# SNES_TST_Sheet1.net
KiCad netlist of a schematic drawn in Altium Designer
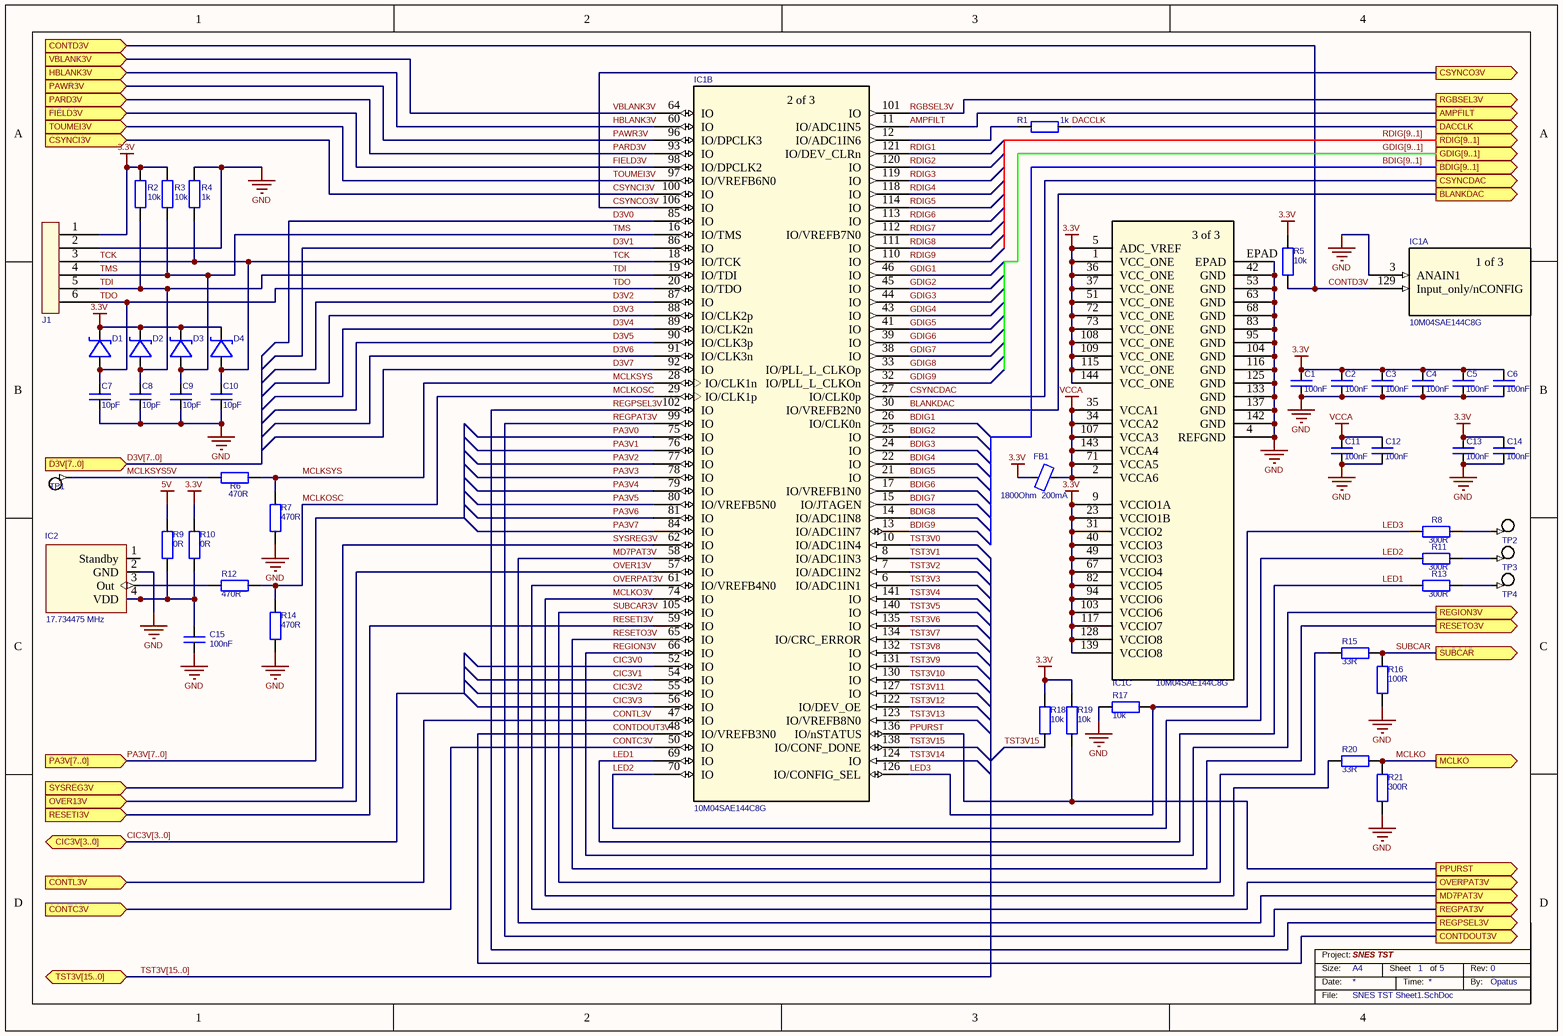
[diagram p0: SNES TST Sheet1.SchDoc]

(export (version "E")
  (design (tool "Eeschema 10.0.6"))
  (components
    (comp (ref "C1")
      (value "100nF")
      (footprint "Cap_0402_Chip")
      (fields (field (name "TOLERANCE") "+-20%"))
      (libsource (lib "PCB") (part "Capacitor"))
    )
    (comp (ref "C2")
      (value "100nF")
      (footprint "Cap_0402_Chip")
      (fields (field (name "TOLERANCE") "+-20%"))
      (libsource (lib "PCB") (part "Capacitor"))
    )
    (comp (ref "C3")
      (value "100nF")
      (footprint "Cap_0402_Chip")
      (fields (field (name "TOLERANCE") "+-20%"))
      (libsource (lib "PCB") (part "Capacitor"))
    )
    (comp (ref "C4")
      (value "100nF")
      (footprint "Cap_0402_Chip")
      (fields (field (name "TOLERANCE") "+-20%"))
      (libsource (lib "PCB") (part "Capacitor"))
    )
    (comp (ref "C5")
      (value "100nF")
      (footprint "Cap_0402_Chip")
      (fields (field (name "TOLERANCE") "+-20%"))
      (libsource (lib "PCB") (part "Capacitor"))
    )
    (comp (ref "C6")
      (value "100nF")
      (footprint "Cap_0402_Chip")
      (fields (field (name "TOLERANCE") "+-20%"))
      (libsource (lib "PCB") (part "Capacitor"))
    )
    (comp (ref "C7")
      (value "10pF")
      (footprint "Cap_0402_Chip")
      (fields (field (name "TOLERANCE") "+-20%"))
      (libsource (lib "PCB") (part "Capacitor"))
    )
    (comp (ref "C8")
      (value "10pF")
      (footprint "Cap_0402_Chip")
      (fields (field (name "TOLERANCE") "+-20%"))
      (libsource (lib "PCB") (part "Capacitor"))
    )
    (comp (ref "C9")
      (value "10pF")
      (footprint "Cap_0402_Chip")
      (fields (field (name "TOLERANCE") "+-20%"))
      (libsource (lib "PCB") (part "Capacitor"))
    )
    (comp (ref "C10")
      (value "10pF")
      (footprint "Cap_0402_Chip")
      (fields (field (name "TOLERANCE") "+-20%"))
      (libsource (lib "PCB") (part "Capacitor"))
    )
    (comp (ref "C11")
      (value "100nF")
      (footprint "Cap_0402_Chip")
      (fields (field (name "TOLERANCE") "+-20%"))
      (libsource (lib "PCB") (part "Capacitor"))
    )
    (comp (ref "C12")
      (value "100nF")
      (footprint "Cap_0402_Chip")
      (fields (field (name "TOLERANCE") "+-20%"))
      (libsource (lib "PCB") (part "Capacitor"))
    )
    (comp (ref "C13")
      (value "100nF")
      (footprint "Cap_0402_Chip")
      (fields (field (name "TOLERANCE") "+-20%"))
      (libsource (lib "PCB") (part "Capacitor"))
    )
    (comp (ref "C14")
      (value "100nF")
      (footprint "Cap_0402_Chip")
      (fields (field (name "TOLERANCE") "+-20%"))
      (libsource (lib "PCB") (part "Capacitor"))
    )
    (comp (ref "C15")
      (value "100nF")
      (footprint "Cap_0402_Chip")
      (fields (field (name "TOLERANCE") "+-20%"))
      (libsource (lib "PCB") (part "Capacitor"))
    )
    (comp (ref "D1")
      (value "Schottky Diode")
      (footprint "SOD323")
      (fields (field (name "MANUFACTURER_PART_NUMBER") "BAT54WS-7-F"))
      (libsource (lib "PCB") (part "Schottky Diode"))
    )
    (comp (ref "D2")
      (value "Schottky Diode")
      (footprint "SOD323")
      (fields (field (name "MANUFACTURER_PART_NUMBER") "BAT54WS-7-F"))
      (libsource (lib "PCB") (part "Schottky Diode"))
    )
    (comp (ref "D3")
      (value "Schottky Diode")
      (footprint "SOD323")
      (fields (field (name "MANUFACTURER_PART_NUMBER") "BAT54WS-7-F"))
      (libsource (lib "PCB") (part "Schottky Diode"))
    )
    (comp (ref "D4")
      (value "Schottky Diode")
      (footprint "SOD323")
      (fields (field (name "MANUFACTURER_PART_NUMBER") "BAT54WS-7-F"))
      (libsource (lib "PCB") (part "Schottky Diode"))
    )
    (comp (ref "FB1")
      (value "1800Ohm  200mA")
      (footprint "Ind_0402_Chip")
      (fields (field (name "MANUFACTURER_PART_NUMBER") "MMZ1005S182ET000"))
      (libsource (lib "PCB") (part "Ferrite Bead"))
    )
    (comp (ref "IC1")
      (value "10M04SAE144C8G")
      (footprint "EQFP-144_A:1P65_")
      (description "No Description Available")
      (fields
        (field (name "MANUFACTURER_PART_NUMBER") "10M08SAE144C8G")
        (field (name "COPYRIGHT") "Copyright (C) 2018 Accelerated Designs. All rights reserved")
      )
      (libsource (lib "") (part "10M08SAE144C8G_1"))
    )
    (comp (ref "IC2")
      (value "17.734475 MHz")
      (footprint "Quarz 7.5mm")
      (description "Oscillator")
      (fields
        (field (name "FREQUENCY") "17.734475 MHz")
        (field (name "MANUFACTURER_PART_NUMBER") "LFSPXO020648Bulk")
      )
      (libsource (lib "PCB") (part "Oscillator"))
    )
    (comp (ref "J1")
      (value "Conn 6P")
      (footprint "Con6P")
      (description "6 Pole Connector")
      (libsource (lib "PCB") (part "Conn 6P"))
    )
    (comp (ref "R1")
      (value "1k")
      (footprint "Res_0402_Chip")
      (fields (field (name "TOLERANCE") "+-1%"))
      (libsource (lib "") (part "R_1"))
    )
    (comp (ref "R2")
      (value "10k")
      (footprint "Res_0402_Chip")
      (fields (field (name "TOLERANCE") "+-1%"))
      (libsource (lib "") (part "R_2"))
    )
    (comp (ref "R3")
      (value "10k")
      (footprint "Res_0402_Chip")
      (fields (field (name "TOLERANCE") "+-1%"))
      (libsource (lib "") (part "R_2"))
    )
    (comp (ref "R4")
      (value "1k")
      (footprint "Res_0402_Chip")
      (fields (field (name "TOLERANCE") "+-1%"))
      (libsource (lib "") (part "R_3"))
    )
    (comp (ref "R5")
      (value "10k")
      (footprint "Res_0402_Chip")
      (fields (field (name "TOLERANCE") "+-1%"))
      (libsource (lib "") (part "R_2"))
    )
    (comp (ref "R6")
      (value "470R")
      (footprint "Res_0603_Chip")
      (fields (field (name "TOLERANCE") "+-1%"))
      (libsource (lib "PCB") (part "R"))
    )
    (comp (ref "R7")
      (value "470R")
      (footprint "Res_0603_Chip")
      (fields (field (name "TOLERANCE") "+-1%"))
      (libsource (lib "") (part "R_2"))
    )
    (comp (ref "R8")
      (value "300R")
      (footprint "Res_0603_Chip")
      (fields (field (name "TOLERANCE") "+-1%"))
      (libsource (lib "PCB") (part "R"))
    )
    (comp (ref "R9") (value "0R") (footprint "Res_0402_Chip") (libsource (lib "") (part "R_2")))
    (comp (ref "R10") (value "0R") (footprint "Res_0402_Chip") (libsource (lib "") (part "R_2")))
    (comp (ref "R11")
      (value "300R")
      (footprint "Res_0603_Chip")
      (fields (field (name "TOLERANCE") "+-1%"))
      (libsource (lib "PCB") (part "R"))
    )
    (comp (ref "R12")
      (value "470R")
      (footprint "Res_0603_Chip")
      (fields (field (name "TOLERANCE") "+-1%"))
      (libsource (lib "PCB") (part "R"))
    )
    (comp (ref "R13")
      (value "300R")
      (footprint "Res_0603_Chip")
      (fields (field (name "TOLERANCE") "+-1%"))
      (libsource (lib "PCB") (part "R"))
    )
    (comp (ref "R14")
      (value "470R")
      (footprint "Res_0603_Chip")
      (fields (field (name "TOLERANCE") "+-1%"))
      (libsource (lib "") (part "R_2"))
    )
    (comp (ref "R15")
      (value "33R")
      (footprint "Res_0603_Chip")
      (fields (field (name "TOLERANCE") "+-1%"))
      (libsource (lib "PCB") (part "R"))
    )
    (comp (ref "R16")
      (value "100R")
      (footprint "Res_0603_Chip")
      (fields (field (name "TOLERANCE") "+-1%"))
      (libsource (lib "") (part "R_2"))
    )
    (comp (ref "R17")
      (value "10k")
      (footprint "Res_0402_Chip")
      (fields (field (name "TOLERANCE") "+-1%"))
      (libsource (lib "") (part "R_1"))
    )
    (comp (ref "R18")
      (value "10k")
      (footprint "Res_0402_Chip")
      (fields (field (name "TOLERANCE") "+-1%"))
      (libsource (lib "") (part "R_2"))
    )
    (comp (ref "R19")
      (value "10k")
      (footprint "Res_0402_Chip")
      (fields (field (name "TOLERANCE") "+-1%"))
      (libsource (lib "") (part "R_2"))
    )
    (comp (ref "R20")
      (value "33R")
      (footprint "Res_0603_Chip")
      (fields (field (name "TOLERANCE") "+-1%"))
      (libsource (lib "PCB") (part "R"))
    )
    (comp (ref "R21")
      (value "300R")
      (footprint "Res_0603_Chip")
      (fields (field (name "TOLERANCE") "+-1%"))
      (libsource (lib "") (part "R_2"))
    )
    (comp (ref "TP1")
      (value "Pin Connector")
      (footprint "Pin Connector Small")
      (libsource (lib "PCB") (part "Pin Connector"))
    )
    (comp (ref "TP2")
      (value "Pin Connector")
      (footprint "Pin Connector Small")
      (libsource (lib "PCB") (part "Pin Connector"))
    )
    (comp (ref "TP3")
      (value "Pin Connector")
      (footprint "Pin Connector Small")
      (libsource (lib "PCB") (part "Pin Connector"))
    )
    (comp (ref "TP4")
      (value "Pin Connector")
      (footprint "Pin Connector Small")
      (libsource (lib "PCB") (part "Pin Connector"))
    )
  )
  (nets
    (net (code "1") (name "/AMPFILT") (class "Default")
      (node (ref "IC1") (pin "11") (pinfunction "IO/ADC1IN5_11") (pintype "output"))
    )
    (net (code "2") (name "/BDIG1") (class "Default")
      (node (ref "IC1") (pin "26") (pinfunction "IO/CLK0n_26") (pintype "output"))
    )
    (net (code "3") (name "/BDIG2") (class "Default")
      (node (ref "IC1") (pin "25") (pinfunction "IO_25") (pintype "output"))
    )
    (net (code "4") (name "/BDIG3") (class "Default")
      (node (ref "IC1") (pin "24") (pinfunction "IO_24") (pintype "output"))
    )
    (net (code "5") (name "/BDIG4") (class "Default")
      (node (ref "IC1") (pin "22") (pinfunction "IO_22") (pintype "output"))
    )
    (net (code "6") (name "/BDIG5") (class "Default")
      (node (ref "IC1") (pin "21") (pinfunction "IO_21") (pintype "output"))
    )
    (net (code "7") (name "/BDIG6") (class "Default")
      (node (ref "IC1") (pin "17") (pinfunction "IO/VREFB1N0_17") (pintype "output"))
    )
    (net (code "8") (name "/BDIG7") (class "Default")
      (node (ref "IC1") (pin "15") (pinfunction "IO/JTAGEN_15") (pintype "output"))
    )
    (net (code "9") (name "/BDIG8") (class "Default")
      (node (ref "IC1") (pin "14") (pinfunction "IO/ADC1IN8_14") (pintype "output"))
    )
    (net (code "10") (name "/BDIG9") (class "Default")
      (node (ref "IC1") (pin "13") (pinfunction "IO/ADC1IN7_13") (pintype "bidirectional"))
    )
    (net (code "12") (name "/BLANKDAC") (class "Default")
      (node (ref "IC1") (pin "30") (pinfunction "IO/VREFB2N0_30") (pintype "output"))
    )
    (net (code "13") (name "/CIC3V0") (class "Default")
      (node (ref "IC1") (pin "52") (pinfunction "IO_52") (pintype "bidirectional"))
    )
    (net (code "14") (name "/CIC3V1") (class "Default")
      (node (ref "IC1") (pin "54") (pinfunction "IO_54") (pintype "bidirectional"))
    )
    (net (code "15") (name "/CIC3V2") (class "Default")
      (node (ref "IC1") (pin "55") (pinfunction "IO_55") (pintype "bidirectional"))
    )
    (net (code "16") (name "/CIC3V3") (class "Default")
      (node (ref "IC1") (pin "56") (pinfunction "IO_56") (pintype "bidirectional"))
    )
    (net (code "18") (name "/CONTC3V") (class "Default")
      (node (ref "IC1") (pin "50") (pinfunction "IO_50") (pintype "bidirectional"))
    )
    (net (code "19") (name "/CONTD3V") (class "Default")
      (node (ref "IC1") (pin "129") (pinfunction "Input_only/nCONFIG_129") (pintype "input"))
      (node (ref "R5") (pin "2") (pintype "passive"))
    )
    (net (code "20") (name "/CONTDOUT3V") (class "Default")
      (node (ref "IC1") (pin "48") (pinfunction "IO/VREFB3N0_48") (pintype "bidirectional"))
    )
    (net (code "21") (name "/CONTL3V") (class "Default")
      (node (ref "IC1") (pin "47") (pinfunction "IO_47") (pintype "bidirectional"))
    )
    (net (code "22") (name "/CSYNCDAC") (class "Default")
      (node (ref "IC1") (pin "27") (pinfunction "IO/CLK0p_27") (pintype "output"))
    )
    (net (code "23") (name "/CSYNCI3V") (class "Default")
      (node (ref "IC1") (pin "100") (pinfunction "IO_100") (pintype "bidirectional"))
    )
    (net (code "24") (name "/CSYNCO3V") (class "Default")
      (node (ref "IC1") (pin "106") (pinfunction "IO_106") (pintype "bidirectional"))
    )
    (net (code "25") (name "/D3V0") (class "Default")
      (node (ref "IC1") (pin "85") (pinfunction "IO_85") (pintype "bidirectional"))
    )
    (net (code "26") (name "/D3V1") (class "Default")
      (node (ref "IC1") (pin "86") (pinfunction "IO_86") (pintype "bidirectional"))
    )
    (net (code "27") (name "/D3V2") (class "Default")
      (node (ref "IC1") (pin "87") (pinfunction "IO_87") (pintype "bidirectional"))
    )
    (net (code "28") (name "/D3V3") (class "Default")
      (node (ref "IC1") (pin "88") (pinfunction "IO/CLK2p_88") (pintype "bidirectional"))
    )
    (net (code "29") (name "/D3V4") (class "Default")
      (node (ref "IC1") (pin "89") (pinfunction "IO/CLK2n_89") (pintype "bidirectional"))
    )
    (net (code "30") (name "/D3V5") (class "Default")
      (node (ref "IC1") (pin "90") (pinfunction "IO/CLK3p_90") (pintype "bidirectional"))
    )
    (net (code "31") (name "/D3V6") (class "Default")
      (node (ref "IC1") (pin "91") (pinfunction "IO/CLK3n_91") (pintype "bidirectional"))
    )
    (net (code "32") (name "/D3V7") (class "Default")
      (node (ref "IC1") (pin "92") (pinfunction "IO_92") (pintype "bidirectional"))
    )
    (net (code "34") (name "/DACCLK") (class "Default") (node (ref "R1") (pin "2") (pintype "passive")))
    (net (code "35") (name "/FIELD3V") (class "Default")
      (node (ref "IC1") (pin "98") (pinfunction "IO/DPCLK2_98") (pintype "bidirectional"))
    )
    (net (code "36") (name "/GDIG1") (class "Default")
      (node (ref "IC1") (pin "46") (pinfunction "IO_46") (pintype "output"))
    )
    (net (code "37") (name "/GDIG2") (class "Default")
      (node (ref "IC1") (pin "45") (pinfunction "IO_45") (pintype "output"))
    )
    (net (code "38") (name "/GDIG3") (class "Default")
      (node (ref "IC1") (pin "44") (pinfunction "IO_44") (pintype "output"))
    )
    (net (code "39") (name "/GDIG4") (class "Default")
      (node (ref "IC1") (pin "43") (pinfunction "IO_43") (pintype "output"))
    )
    (net (code "40") (name "/GDIG5") (class "Default")
      (node (ref "IC1") (pin "41") (pinfunction "IO_41") (pintype "output"))
    )
    (net (code "41") (name "/GDIG6") (class "Default")
      (node (ref "IC1") (pin "39") (pinfunction "IO_39") (pintype "output"))
    )
    (net (code "42") (name "/GDIG7") (class "Default")
      (node (ref "IC1") (pin "38") (pinfunction "IO_38") (pintype "output"))
    )
    (net (code "43") (name "/GDIG8") (class "Default")
      (node (ref "IC1") (pin "33") (pinfunction "IO/PLL_L_CLKOp_33") (pintype "output"))
    )
    (net (code "44") (name "/GDIG9") (class "Default")
      (node (ref "IC1") (pin "32") (pinfunction "IO/PLL_L_CLKOn_32") (pintype "output"))
    )
    (net (code "46") (name "/HBLANK3V") (class "Default")
      (node (ref "IC1") (pin "60") (pinfunction "IO_60") (pintype "bidirectional"))
    )
    (net (code "47") (name "/LED1") (class "Default")
      (node (ref "IC1") (pin "69") (pinfunction "IO_69") (pintype "bidirectional"))
      (node (ref "R13") (pin "2") (pintype "passive"))
    )
    (net (code "48") (name "/LED2") (class "Default")
      (node (ref "IC1") (pin "70") (pinfunction "IO_70") (pintype "bidirectional"))
      (node (ref "R11") (pin "2") (pintype "passive"))
    )
    (net (code "49") (name "/LED3") (class "Default")
      (node (ref "IC1") (pin "126") (pinfunction "IO/CONFIG_SEL_126") (pintype "bidirectional"))
      (node (ref "R17") (pin "2") (pintype "passive"))
      (node (ref "R8") (pin "2") (pintype "passive"))
    )
    (net (code "50") (name "/MCLKO") (class "Default")
      (node (ref "R20") (pin "1") (pintype "passive"))
      (node (ref "R21") (pin "1") (pintype "passive"))
    )
    (net (code "51") (name "/MCLKO3V") (class "Default")
      (node (ref "IC1") (pin "74") (pinfunction "IO_74") (pintype "bidirectional"))
      (node (ref "R20") (pin "2") (pintype "passive"))
    )
    (net (code "52") (name "/MCLKOSC") (class "Default")
      (node (ref "IC1") (pin "29") (pinfunction "IO/CLK1p_29") (pintype "bidirectional"))
      (node (ref "R12") (pin "1") (pintype "passive"))
      (node (ref "R14") (pin "1") (pintype "passive"))
    )
    (net (code "53") (name "/MCLKSYS") (class "Default")
      (node (ref "IC1") (pin "28") (pinfunction "IO/CLK1n_28") (pintype "bidirectional"))
      (node (ref "R6") (pin "1") (pintype "passive"))
      (node (ref "R7") (pin "1") (pintype "passive"))
    )
    (net (code "54") (name "/MCLKSYS5V") (class "Default")
      (node (ref "R6") (pin "2") (pintype "passive"))
      (node (ref "TP1") (pin "1") (pinfunction "0_1") (pintype "output"))
    )
    (net (code "55") (name "/MD7PAT3V") (class "Default")
      (node (ref "IC1") (pin "58") (pinfunction "IO_58") (pintype "bidirectional"))
    )
    (net (code "56") (name "/OVER13V") (class "Default")
      (node (ref "IC1") (pin "57") (pinfunction "IO_57") (pintype "bidirectional"))
    )
    (net (code "57") (name "/OVERPAT3V") (class "Default")
      (node (ref "IC1") (pin "61") (pinfunction "IO/VREFB4N0_61") (pintype "bidirectional"))
    )
    (net (code "58") (name "/PA3V0") (class "Default")
      (node (ref "IC1") (pin "75") (pinfunction "IO_75") (pintype "bidirectional"))
    )
    (net (code "59") (name "/PA3V1") (class "Default")
      (node (ref "IC1") (pin "76") (pinfunction "IO_76") (pintype "bidirectional"))
    )
    (net (code "60") (name "/PA3V2") (class "Default")
      (node (ref "IC1") (pin "77") (pinfunction "IO_77") (pintype "bidirectional"))
    )
    (net (code "61") (name "/PA3V3") (class "Default")
      (node (ref "IC1") (pin "78") (pinfunction "IO_78") (pintype "bidirectional"))
    )
    (net (code "62") (name "/PA3V4") (class "Default")
      (node (ref "IC1") (pin "79") (pinfunction "IO_79") (pintype "bidirectional"))
    )
    (net (code "63") (name "/PA3V5") (class "Default")
      (node (ref "IC1") (pin "80") (pinfunction "IO/VREFB5N0_80") (pintype "bidirectional"))
    )
    (net (code "64") (name "/PA3V6") (class "Default")
      (node (ref "IC1") (pin "81") (pinfunction "IO_81") (pintype "bidirectional"))
    )
    (net (code "65") (name "/PA3V7") (class "Default")
      (node (ref "IC1") (pin "84") (pinfunction "IO_84") (pintype "bidirectional"))
    )
    (net (code "67") (name "/PARD3V") (class "Default")
      (node (ref "IC1") (pin "93") (pinfunction "IO_93") (pintype "bidirectional"))
    )
    (net (code "68") (name "/PAWR3V") (class "Default")
      (node (ref "IC1") (pin "96") (pinfunction "IO/DPCLK3_96") (pintype "bidirectional"))
    )
    (net (code "69") (name "/PPURST") (class "Default")
      (node (ref "IC1") (pin "136") (pinfunction "IO/nSTATUS_136") (pintype "bidirectional"))
      (node (ref "R19") (pin "2") (pintype "passive"))
    )
    (net (code "70") (name "/RDIG1") (class "Default")
      (node (ref "IC1") (pin "121") (pinfunction "IO/DEV_CLRn_121") (pintype "output"))
    )
    (net (code "71") (name "/RDIG2") (class "Default")
      (node (ref "IC1") (pin "120") (pinfunction "IO_120") (pintype "output"))
    )
    (net (code "72") (name "/RDIG3") (class "Default")
      (node (ref "IC1") (pin "119") (pinfunction "IO_119") (pintype "output"))
    )
    (net (code "73") (name "/RDIG4") (class "Default")
      (node (ref "IC1") (pin "118") (pinfunction "IO_118") (pintype "output"))
    )
    (net (code "74") (name "/RDIG5") (class "Default")
      (node (ref "IC1") (pin "114") (pinfunction "IO_114") (pintype "output"))
    )
    (net (code "75") (name "/RDIG6") (class "Default")
      (node (ref "IC1") (pin "113") (pinfunction "IO_113") (pintype "output"))
    )
    (net (code "76") (name "/RDIG7") (class "Default")
      (node (ref "IC1") (pin "112") (pinfunction "IO/VREFB7N0_112") (pintype "output"))
    )
    (net (code "77") (name "/RDIG8") (class "Default")
      (node (ref "IC1") (pin "111") (pinfunction "IO_111") (pintype "output"))
    )
    (net (code "78") (name "/RDIG9") (class "Default")
      (node (ref "IC1") (pin "110") (pinfunction "IO_110") (pintype "output"))
    )
    (net (code "80") (name "/REGION3V") (class "Default")
      (node (ref "IC1") (pin "66") (pinfunction "IO_66") (pintype "bidirectional"))
    )
    (net (code "81") (name "/REGPAT3V") (class "Default")
      (node (ref "IC1") (pin "99") (pinfunction "IO_99") (pintype "bidirectional"))
    )
    (net (code "82") (name "/REGPSEL3V") (class "Default")
      (node (ref "IC1") (pin "102") (pinfunction "IO_102") (pintype "bidirectional"))
    )
    (net (code "83") (name "/RESETI3V") (class "Default")
      (node (ref "IC1") (pin "59") (pinfunction "IO_59") (pintype "bidirectional"))
    )
    (net (code "84") (name "/RESETO3V") (class "Default")
      (node (ref "IC1") (pin "65") (pinfunction "IO_65") (pintype "bidirectional"))
    )
    (net (code "85") (name "/RGBSEL3V") (class "Default")
      (node (ref "IC1") (pin "101") (pinfunction "IO_101") (pintype "output"))
    )
    (net (code "86") (name "/SUBCAR") (class "Default")
      (node (ref "R15") (pin "1") (pintype "passive"))
      (node (ref "R16") (pin "1") (pintype "passive"))
    )
    (net (code "87") (name "/SUBCAR3V") (class "Default")
      (node (ref "IC1") (pin "105") (pinfunction "IO_105") (pintype "bidirectional"))
      (node (ref "R15") (pin "2") (pintype "passive"))
    )
    (net (code "88") (name "/SYSREG3V") (class "Default")
      (node (ref "IC1") (pin "62") (pinfunction "IO_62") (pintype "bidirectional"))
    )
    (net (code "89") (name "/TCK") (class "Default")
      (node (ref "C10") (pin "1") (pintype "passive"))
      (node (ref "D4") (pin "2") (pinfunction "A_2") (pintype "passive"))
      (node (ref "IC1") (pin "18") (pinfunction "IO/TCK_18") (pintype "bidirectional"))
      (node (ref "J1") (pin "3") (pintype "passive"))
      (node (ref "R4") (pin "1") (pintype "passive"))
    )
    (net (code "90") (name "/TDI") (class "Default")
      (node (ref "C8") (pin "1") (pintype "passive"))
      (node (ref "D2") (pin "2") (pinfunction "A_2") (pintype "passive"))
      (node (ref "IC1") (pin "19") (pinfunction "IO/TDI_19") (pintype "bidirectional"))
      (node (ref "J1") (pin "5") (pintype "passive"))
      (node (ref "R2") (pin "2") (pintype "passive"))
    )
    (net (code "91") (name "/TDO") (class "Default")
      (node (ref "C7") (pin "1") (pintype "passive"))
      (node (ref "D1") (pin "2") (pinfunction "A_2") (pintype "passive"))
      (node (ref "IC1") (pin "20") (pinfunction "IO/TDO_20") (pintype "bidirectional"))
      (node (ref "J1") (pin "6") (pintype "passive"))
    )
    (net (code "92") (name "/TMS") (class "Default")
      (node (ref "C9") (pin "1") (pintype "passive"))
      (node (ref "D3") (pin "2") (pinfunction "A_2") (pintype "passive"))
      (node (ref "IC1") (pin "16") (pinfunction "IO/TMS_16") (pintype "bidirectional"))
      (node (ref "J1") (pin "4") (pintype "passive"))
      (node (ref "R3") (pin "2") (pintype "passive"))
    )
    (net (code "93") (name "/TOUMEI3V") (class "Default")
      (node (ref "IC1") (pin "97") (pinfunction "IO/VREFB6N0_97") (pintype "bidirectional"))
    )
    (net (code "94") (name "/TST3V0") (class "Default")
      (node (ref "IC1") (pin "10") (pinfunction "IO/ADC1IN4_10") (pintype "input"))
    )
    (net (code "95") (name "/TST3V1") (class "Default")
      (node (ref "IC1") (pin "8") (pinfunction "IO/ADC1IN3_8") (pintype "input"))
    )
    (net (code "96") (name "/TST3V2") (class "Default")
      (node (ref "IC1") (pin "7") (pinfunction "IO/ADC1IN2_7") (pintype "input"))
    )
    (net (code "97") (name "/TST3V3") (class "Default")
      (node (ref "IC1") (pin "6") (pinfunction "IO/ADC1IN1_6") (pintype "input"))
    )
    (net (code "98") (name "/TST3V4") (class "Default")
      (node (ref "IC1") (pin "141") (pinfunction "IO_141") (pintype "input"))
    )
    (net (code "99") (name "/TST3V5") (class "Default")
      (node (ref "IC1") (pin "140") (pinfunction "IO_140") (pintype "input"))
    )
    (net (code "100") (name "/TST3V6") (class "Default")
      (node (ref "IC1") (pin "135") (pinfunction "IO_135") (pintype "input"))
    )
    (net (code "101") (name "/TST3V7") (class "Default")
      (node (ref "IC1") (pin "134") (pinfunction "IO/CRC_ERROR_134") (pintype "input"))
    )
    (net (code "102") (name "/TST3V8") (class "Default")
      (node (ref "IC1") (pin "132") (pinfunction "IO_132") (pintype "input"))
    )
    (net (code "103") (name "/TST3V9") (class "Default")
      (node (ref "IC1") (pin "131") (pinfunction "IO_131") (pintype "input"))
    )
    (net (code "104") (name "/TST3V10") (class "Default")
      (node (ref "IC1") (pin "130") (pinfunction "IO_130") (pintype "input"))
    )
    (net (code "105") (name "/TST3V11") (class "Default")
      (node (ref "IC1") (pin "127") (pinfunction "IO_127") (pintype "input"))
    )
    (net (code "106") (name "/TST3V12") (class "Default")
      (node (ref "IC1") (pin "122") (pinfunction "IO/DEV_OE_122") (pintype "input"))
    )
    (net (code "107") (name "/TST3V13") (class "Default")
      (node (ref "IC1") (pin "123") (pinfunction "IO/VREFB8N0_123") (pintype "input"))
    )
    (net (code "108") (name "/TST3V14") (class "Default")
      (node (ref "IC1") (pin "124") (pinfunction "IO_124") (pintype "input"))
    )
    (net (code "109") (name "/TST3V15") (class "Default")
      (node (ref "IC1") (pin "138") (pinfunction "IO/CONF_DONE_138") (pintype "bidirectional"))
      (node (ref "R18") (pin "2") (pintype "passive"))
    )
    (net (code "111") (name "/VBLANK3V") (class "Default")
      (node (ref "IC1") (pin "64") (pinfunction "IO_64") (pintype "bidirectional"))
    )
    (net (code "112") (name "3.3V") (class "Default")
      (node (ref "C1") (pin "1") (pintype "passive"))
      (node (ref "C13") (pin "1") (pintype "passive"))
      (node (ref "C14") (pin "1") (pintype "passive"))
      (node (ref "C2") (pin "1") (pintype "passive"))
      (node (ref "C3") (pin "1") (pintype "passive"))
      (node (ref "C4") (pin "1") (pintype "passive"))
      (node (ref "C5") (pin "1") (pintype "passive"))
      (node (ref "C6") (pin "1") (pintype "passive"))
      (node (ref "D1") (pin "1") (pinfunction "K_1") (pintype "passive"))
      (node (ref "D2") (pin "1") (pinfunction "K_1") (pintype "passive"))
      (node (ref "D3") (pin "1") (pinfunction "K_1") (pintype "passive"))
      (node (ref "D4") (pin "1") (pinfunction "K_1") (pintype "passive"))
      (node (ref "FB1") (pin "1") (pintype "passive"))
      (node (ref "IC1") (pin "1") (pinfunction "VCC_ONE_1") (pintype "power_in"))
      (node (ref "IC1") (pin "103") (pinfunction "VCCIO6_103") (pintype "power_in"))
      (node (ref "IC1") (pin "108") (pinfunction "VCC_ONE_108") (pintype "power_in"))
      (node (ref "IC1") (pin "109") (pinfunction "VCC_ONE_109") (pintype "power_in"))
      (node (ref "IC1") (pin "115") (pinfunction "VCC_ONE_115") (pintype "power_in"))
      (node (ref "IC1") (pin "117") (pinfunction "VCCIO7_117") (pintype "power_in"))
      (node (ref "IC1") (pin "128") (pinfunction "VCCIO8_128") (pintype "power_in"))
      (node (ref "IC1") (pin "139") (pinfunction "VCCIO8_139") (pintype "power_in"))
      (node (ref "IC1") (pin "144") (pinfunction "VCC_ONE_144") (pintype "power_in"))
      (node (ref "IC1") (pin "23") (pinfunction "VCCIO1B_23") (pintype "power_in"))
      (node (ref "IC1") (pin "31") (pinfunction "VCCIO2_31") (pintype "power_in"))
      (node (ref "IC1") (pin "36") (pinfunction "VCC_ONE_36") (pintype "power_in"))
      (node (ref "IC1") (pin "37") (pinfunction "VCC_ONE_37") (pintype "power_in"))
      (node (ref "IC1") (pin "40") (pinfunction "VCCIO3_40") (pintype "power_in"))
      (node (ref "IC1") (pin "49") (pinfunction "VCCIO3_49") (pintype "power_in"))
      (node (ref "IC1") (pin "5") (pinfunction "ADC_VREF_5") (pintype "power_in"))
      (node (ref "IC1") (pin "51") (pinfunction "VCC_ONE_51") (pintype "power_in"))
      (node (ref "IC1") (pin "67") (pinfunction "VCCIO4_67") (pintype "power_in"))
      (node (ref "IC1") (pin "72") (pinfunction "VCC_ONE_72") (pintype "power_in"))
      (node (ref "IC1") (pin "73") (pinfunction "VCC_ONE_73") (pintype "power_in"))
      (node (ref "IC1") (pin "82") (pinfunction "VCCIO5_82") (pintype "power_in"))
      (node (ref "IC1") (pin "9") (pinfunction "VCCIO1A_9") (pintype "power_in"))
      (node (ref "IC1") (pin "94") (pinfunction "VCCIO6_94") (pintype "power_in"))
      (node (ref "J1") (pin "1") (pintype "passive"))
      (node (ref "R10") (pin "1") (pintype "passive"))
      (node (ref "R18") (pin "1") (pintype "passive"))
      (node (ref "R19") (pin "1") (pintype "passive"))
      (node (ref "R2") (pin "1") (pintype "passive"))
      (node (ref "R3") (pin "1") (pintype "passive"))
      (node (ref "R5") (pin "1") (pintype "passive"))
    )
    (net (code "113") (name "5V") (class "Default") (node (ref "R9") (pin "1") (pintype "passive")))
    (net (code "114") (name "GND") (class "Default")
      (node (ref "C1") (pin "2") (pintype "passive"))
      (node (ref "C10") (pin "2") (pintype "passive"))
      (node (ref "C11") (pin "2") (pintype "passive"))
      (node (ref "C12") (pin "2") (pintype "passive"))
      (node (ref "C13") (pin "2") (pintype "passive"))
      (node (ref "C14") (pin "2") (pintype "passive"))
      (node (ref "C15") (pin "2") (pintype "passive"))
      (node (ref "C2") (pin "2") (pintype "passive"))
      (node (ref "C3") (pin "2") (pintype "passive"))
      (node (ref "C4") (pin "2") (pintype "passive"))
      (node (ref "C5") (pin "2") (pintype "passive"))
      (node (ref "C6") (pin "2") (pintype "passive"))
      (node (ref "C7") (pin "2") (pintype "passive"))
      (node (ref "C8") (pin "2") (pintype "passive"))
      (node (ref "C9") (pin "2") (pintype "passive"))
      (node (ref "IC1") (pin "104") (pinfunction "GND_104") (pintype "power_in"))
      (node (ref "IC1") (pin "116") (pinfunction "GND_116") (pintype "power_in"))
      (node (ref "IC1") (pin "125") (pinfunction "GND_125") (pintype "power_in"))
      (node (ref "IC1") (pin "133") (pinfunction "GND_133") (pintype "power_in"))
      (node (ref "IC1") (pin "137") (pinfunction "GND_137") (pintype "power_in"))
      (node (ref "IC1") (pin "142") (pinfunction "GND_142") (pintype "power_in"))
      (node (ref "IC1") (pin "3") (pinfunction "ANAIN1_3") (pintype "input"))
      (node (ref "IC1") (pin "4") (pinfunction "REFGND_4") (pintype "power_in"))
      (node (ref "IC1") (pin "42") (pinfunction "GND_42") (pintype "power_in"))
      (node (ref "IC1") (pin "53") (pinfunction "GND_53") (pintype "power_in"))
      (node (ref "IC1") (pin "63") (pinfunction "GND_63") (pintype "power_in"))
      (node (ref "IC1") (pin "68") (pinfunction "GND_68") (pintype "power_in"))
      (node (ref "IC1") (pin "83") (pinfunction "GND_83") (pintype "power_in"))
      (node (ref "IC1") (pin "95") (pinfunction "GND_95") (pintype "power_in"))
      (node (ref "IC1") (pin "EPAD") (pinfunction "EPAD_EPAD") (pintype "power_in"))
      (node (ref "IC2") (pin "2") (pinfunction "GND_2") (pintype "power_in"))
      (node (ref "J1") (pin "2") (pintype "passive"))
      (node (ref "R14") (pin "2") (pintype "passive"))
      (node (ref "R16") (pin "2") (pintype "passive"))
      (node (ref "R17") (pin "1") (pintype "passive"))
      (node (ref "R21") (pin "2") (pintype "passive"))
      (node (ref "R4") (pin "2") (pintype "passive"))
      (node (ref "R7") (pin "2") (pintype "passive"))
    )
    (net (code "115") (name "Net-(IC1B-IO{slash}ADC1IN6)") (class "Default")
      (node (ref "IC1") (pin "12") (pinfunction "IO/ADC1IN6_12") (pintype "output"))
      (node (ref "R1") (pin "1") (pintype "passive"))
    )
    (net (code "116") (name "Net-(IC2-Out)") (class "Default")
      (node (ref "IC2") (pin "3") (pinfunction "Out_3") (pintype "output"))
      (node (ref "R12") (pin "2") (pintype "passive"))
    )
    (net (code "117") (name "Net-(IC2-VDD)") (class "Default")
      (node (ref "C15") (pin "1") (pintype "passive"))
      (node (ref "IC2") (pin "4") (pinfunction "VDD_4") (pintype "power_in"))
      (node (ref "R10") (pin "2") (pintype "passive"))
      (node (ref "R9") (pin "2") (pintype "passive"))
    )
    (net (code "118") (name "Net-(TP2-0)") (class "Default")
      (node (ref "R8") (pin "1") (pintype "passive"))
      (node (ref "TP2") (pin "1") (pinfunction "0_1") (pintype "output"))
    )
    (net (code "119") (name "Net-(TP3-0)") (class "Default")
      (node (ref "R11") (pin "1") (pintype "passive"))
      (node (ref "TP3") (pin "1") (pinfunction "0_1") (pintype "output"))
    )
    (net (code "120") (name "Net-(TP4-0)") (class "Default")
      (node (ref "R13") (pin "1") (pintype "passive"))
      (node (ref "TP4") (pin "1") (pinfunction "0_1") (pintype "output"))
    )
    (net (code "121") (name "VCCA") (class "Default")
      (node (ref "C11") (pin "1") (pintype "passive"))
      (node (ref "C12") (pin "1") (pintype "passive"))
      (node (ref "FB1") (pin "2") (pintype "passive"))
      (node (ref "IC1") (pin "107") (pinfunction "VCCA3_107") (pintype "power_in"))
      (node (ref "IC1") (pin "143") (pinfunction "VCCA4_143") (pintype "power_in"))
      (node (ref "IC1") (pin "2") (pinfunction "VCCA6_2") (pintype "power_in"))
      (node (ref "IC1") (pin "34") (pinfunction "VCCA2_34") (pintype "power_in"))
      (node (ref "IC1") (pin "35") (pinfunction "VCCA1_35") (pintype "power_in"))
      (node (ref "IC1") (pin "71") (pinfunction "VCCA5_71") (pintype "power_in"))
    )
    (net (code "122") (name "unconnected-(IC2-Standby-Pad1)") (class "Default")
      (node (ref "IC2") (pin "1") (pinfunction "Standby_1") (pintype "passive"))
    )
  )
)
